# mister_io_db9.net
KiCad netlist of a schematic drawn in EAGLE
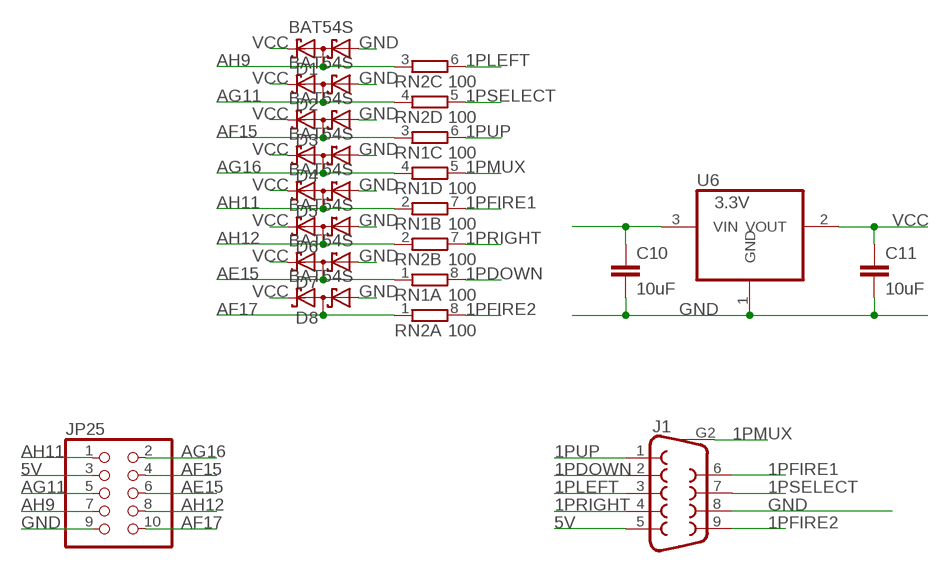
[diagram p0: schematic, sheet 1]

(export (version "E")
  (design (tool "Eeschema 10.0.6"))
  (components
    (comp (ref "C10")
      (value "10uF")
      (footprint "eagle-import:C0603K")
      (libsource (lib "eagle-import") (part "C-EUC0603K"))
    )
    (comp (ref "C11")
      (value "10uF")
      (footprint "eagle-import:C0603K")
      (libsource (lib "eagle-import") (part "C-EUC0603K"))
    )
    (comp (ref "D1")
      (value "BAT54S")
      (footprint "eagle-import:SOT23")
      (libsource (lib "eagle-import") (part "BAT54S"))
    )
    (comp (ref "D2")
      (value "BAT54S")
      (footprint "eagle-import:SOT23")
      (libsource (lib "eagle-import") (part "BAT54S"))
    )
    (comp (ref "D3")
      (value "BAT54S")
      (footprint "eagle-import:SOT23")
      (libsource (lib "eagle-import") (part "BAT54S"))
    )
    (comp (ref "D4")
      (value "BAT54S")
      (footprint "eagle-import:SOT23")
      (libsource (lib "eagle-import") (part "BAT54S"))
    )
    (comp (ref "D5")
      (value "BAT54S")
      (footprint "eagle-import:SOT23")
      (libsource (lib "eagle-import") (part "BAT54S"))
    )
    (comp (ref "D6")
      (value "BAT54S")
      (footprint "eagle-import:SOT23")
      (libsource (lib "eagle-import") (part "BAT54S"))
    )
    (comp (ref "D7")
      (value "BAT54S")
      (footprint "eagle-import:SOT23")
      (libsource (lib "eagle-import") (part "BAT54S"))
    )
    (comp (ref "D8")
      (value "BAT54S")
      (footprint "eagle-import:SOT23")
      (libsource (lib "eagle-import") (part "BAT54S"))
    )
    (comp (ref "J1")
      (value "SPARKFUN-CONNECTORS_DB9MALE")
      (footprint "eagle-import:SPARKFUN-CONNECTORS_DB9_MALE")
      (libsource (lib "eagle-import") (part "SPARKFUN-CONNECTORS_DB9MALE"))
    )
    (comp (ref "JP25")
      (value "PINHD-2X5")
      (footprint "eagle-import:2X05")
      (libsource (lib "eagle-import") (part "PINHD-2X5"))
    )
    (comp (ref "RN1")
      (value "100")
      (footprint "eagle-import:0603-ARC")
      (libsource (lib "eagle-import") (part "4R-N0603-ARC"))
    )
    (comp (ref "RN2")
      (value "100")
      (footprint "eagle-import:0603-ARC")
      (libsource (lib "eagle-import") (part "4R-N0603-ARC"))
    )
    (comp (ref "U6")
      (value "3.3V")
      (footprint "eagle-import:SOT223")
      (fields (field (name "MPN") "REG1117"))
      (libsource (lib "eagle-import") (part "REG1117"))
    )
  )
  (nets
    (net (code "1") (name "/1PDOWN") (class "Default")
      (node (ref "J1") (pin "2") (pinfunction "2_2") (pintype "passive"))
      (node (ref "RN1") (pin "8") (pinfunction "2_8") (pintype "passive"))
    )
    (net (code "2") (name "/1PFIRE1") (class "Default")
      (node (ref "J1") (pin "6") (pinfunction "6_6") (pintype "passive"))
      (node (ref "RN1") (pin "7") (pinfunction "2_7") (pintype "passive"))
    )
    (net (code "3") (name "/1PFIRE2") (class "Default")
      (node (ref "J1") (pin "9") (pinfunction "9_9") (pintype "passive"))
      (node (ref "RN2") (pin "8") (pinfunction "2_8") (pintype "passive"))
    )
    (net (code "4") (name "/1PLEFT") (class "Default")
      (node (ref "J1") (pin "3") (pinfunction "3_3") (pintype "passive"))
      (node (ref "RN2") (pin "6") (pinfunction "2_6") (pintype "passive"))
    )
    (net (code "5") (name "/1PMUX") (class "Default")
      (node (ref "J1") (pin "G2") (pinfunction "10_G2") (pintype "passive"))
      (node (ref "RN1") (pin "5") (pinfunction "2_5") (pintype "passive"))
    )
    (net (code "6") (name "/1PRIGHT") (class "Default")
      (node (ref "J1") (pin "4") (pinfunction "4_4") (pintype "passive"))
      (node (ref "RN2") (pin "7") (pinfunction "2_7") (pintype "passive"))
    )
    (net (code "7") (name "/1PSELECT") (class "Default")
      (node (ref "J1") (pin "7") (pinfunction "7_7") (pintype "passive"))
      (node (ref "RN2") (pin "5") (pinfunction "2_5") (pintype "passive"))
    )
    (net (code "8") (name "/1PUP") (class "Default")
      (node (ref "J1") (pin "1") (pinfunction "1_1") (pintype "passive"))
      (node (ref "RN1") (pin "6") (pinfunction "2_6") (pintype "passive"))
    )
    (net (code "9") (name "/5V") (class "Default")
      (node (ref "C10") (pin "1") (pinfunction "1_1") (pintype "passive"))
      (node (ref "J1") (pin "5") (pinfunction "5_5") (pintype "passive"))
      (node (ref "JP25") (pin "3") (pinfunction "3_3") (pintype "passive"))
      (node (ref "U6") (pin "3") (pinfunction "VIN_3") (pintype "input"))
    )
    (net (code "10") (name "/AE15") (class "Default")
      (node (ref "D7") (pin "3") (pinfunction "C1A2_3") (pintype "passive"))
      (node (ref "JP25") (pin "6") (pinfunction "6_6") (pintype "passive"))
      (node (ref "RN1") (pin "1") (pinfunction "1_1") (pintype "passive"))
    )
    (net (code "11") (name "/AF15") (class "Default")
      (node (ref "D3") (pin "3") (pinfunction "C1A2_3") (pintype "passive"))
      (node (ref "JP25") (pin "4") (pinfunction "4_4") (pintype "passive"))
      (node (ref "RN1") (pin "3") (pinfunction "1_3") (pintype "passive"))
    )
    (net (code "12") (name "/AF17") (class "Default")
      (node (ref "D8") (pin "3") (pinfunction "C1A2_3") (pintype "passive"))
      (node (ref "JP25") (pin "10") (pinfunction "10_10") (pintype "passive"))
      (node (ref "RN2") (pin "1") (pinfunction "1_1") (pintype "passive"))
    )
    (net (code "13") (name "/AG11") (class "Default")
      (node (ref "D2") (pin "3") (pinfunction "C1A2_3") (pintype "passive"))
      (node (ref "JP25") (pin "5") (pinfunction "5_5") (pintype "passive"))
      (node (ref "RN2") (pin "4") (pinfunction "1_4") (pintype "passive"))
    )
    (net (code "14") (name "/AG16") (class "Default")
      (node (ref "D4") (pin "3") (pinfunction "C1A2_3") (pintype "passive"))
      (node (ref "JP25") (pin "2") (pinfunction "2_2") (pintype "passive"))
      (node (ref "RN1") (pin "4") (pinfunction "1_4") (pintype "passive"))
    )
    (net (code "15") (name "/AH9") (class "Default")
      (node (ref "D1") (pin "3") (pinfunction "C1A2_3") (pintype "passive"))
      (node (ref "JP25") (pin "7") (pinfunction "7_7") (pintype "passive"))
      (node (ref "RN2") (pin "3") (pinfunction "1_3") (pintype "passive"))
    )
    (net (code "16") (name "/AH11") (class "Default")
      (node (ref "D5") (pin "3") (pinfunction "C1A2_3") (pintype "passive"))
      (node (ref "JP25") (pin "1") (pinfunction "1_1") (pintype "passive"))
      (node (ref "RN1") (pin "2") (pinfunction "1_2") (pintype "passive"))
    )
    (net (code "17") (name "/AH12") (class "Default")
      (node (ref "D6") (pin "3") (pinfunction "C1A2_3") (pintype "passive"))
      (node (ref "JP25") (pin "8") (pinfunction "8_8") (pintype "passive"))
      (node (ref "RN2") (pin "2") (pinfunction "1_2") (pintype "passive"))
    )
    (net (code "18") (name "/GND") (class "Default")
      (node (ref "C10") (pin "2") (pinfunction "2_2") (pintype "passive"))
      (node (ref "C11") (pin "2") (pinfunction "2_2") (pintype "passive"))
      (node (ref "D1") (pin "1") (pinfunction "A1_1") (pintype "passive"))
      (node (ref "D2") (pin "1") (pinfunction "A1_1") (pintype "passive"))
      (node (ref "D3") (pin "1") (pinfunction "A1_1") (pintype "passive"))
      (node (ref "D4") (pin "1") (pinfunction "A1_1") (pintype "passive"))
      (node (ref "D5") (pin "1") (pinfunction "A1_1") (pintype "passive"))
      (node (ref "D6") (pin "1") (pinfunction "A1_1") (pintype "passive"))
      (node (ref "D7") (pin "1") (pinfunction "A1_1") (pintype "passive"))
      (node (ref "D8") (pin "1") (pinfunction "A1_1") (pintype "passive"))
      (node (ref "J1") (pin "8") (pinfunction "8_8") (pintype "passive"))
      (node (ref "JP25") (pin "9") (pinfunction "9_9") (pintype "passive"))
      (node (ref "U6") (pin "1") (pinfunction "GND_1") (pintype "power_in"))
    )
    (net (code "19") (name "/VCC") (class "Default")
      (node (ref "C11") (pin "1") (pinfunction "1_1") (pintype "passive"))
      (node (ref "D1") (pin "2") (pinfunction "C2_2") (pintype "passive"))
      (node (ref "D2") (pin "2") (pinfunction "C2_2") (pintype "passive"))
      (node (ref "D3") (pin "2") (pinfunction "C2_2") (pintype "passive"))
      (node (ref "D4") (pin "2") (pinfunction "C2_2") (pintype "passive"))
      (node (ref "D5") (pin "2") (pinfunction "C2_2") (pintype "passive"))
      (node (ref "D6") (pin "2") (pinfunction "C2_2") (pintype "passive"))
      (node (ref "D7") (pin "2") (pinfunction "C2_2") (pintype "passive"))
      (node (ref "D8") (pin "2") (pinfunction "C2_2") (pintype "passive"))
      (node (ref "U6") (pin "2") (pinfunction "VOUT_2") (pintype "output"))
    )
  )
)
